# DAC.net
KiCad netlist of a schematic drawn in Altium Designer
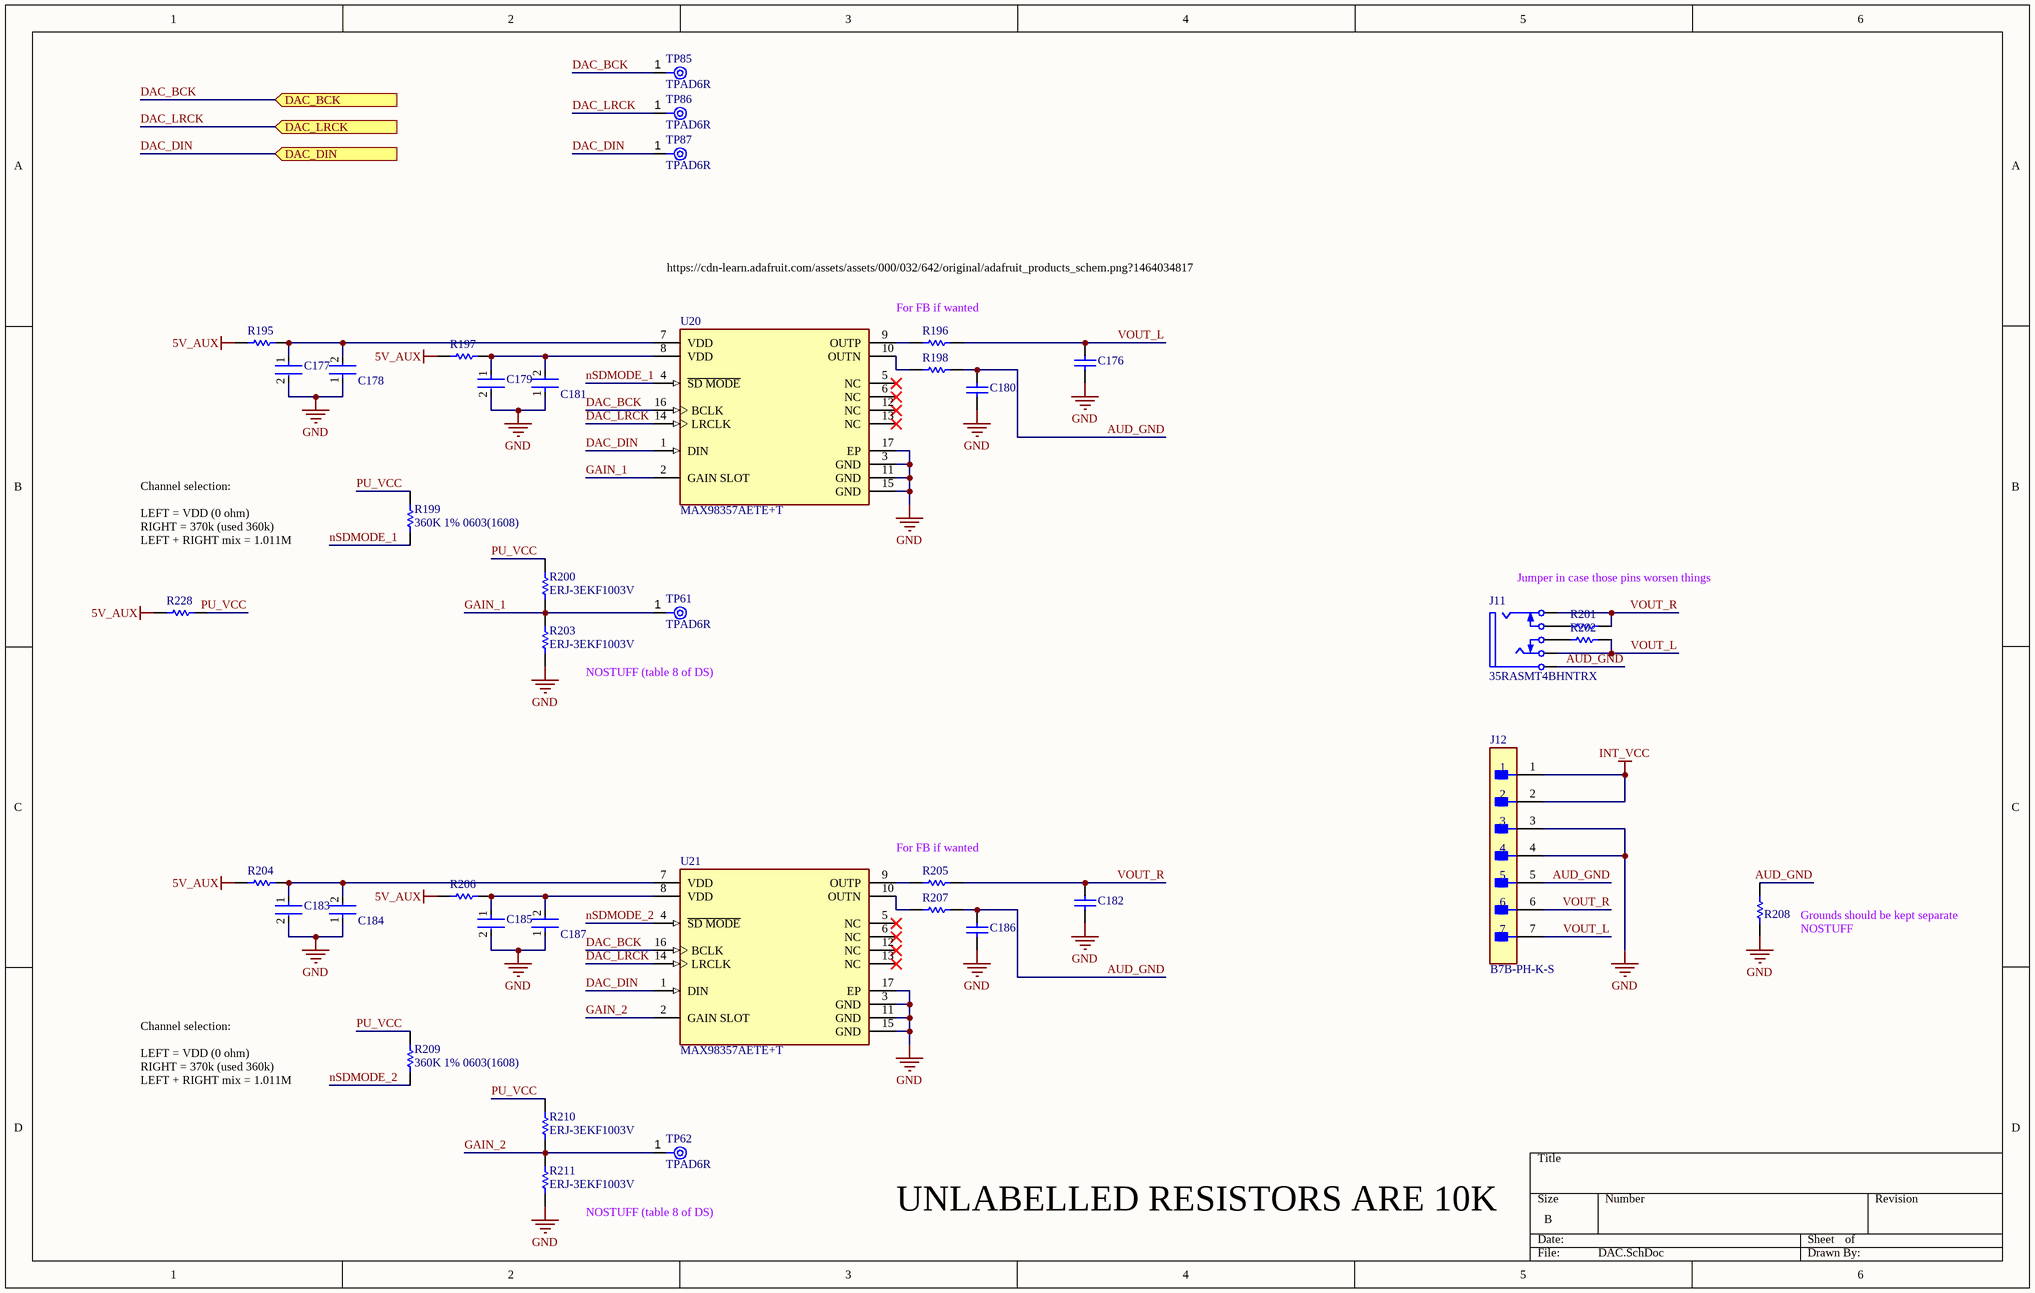
[diagram p0: DAC.SchDoc]

(export (version "E")
  (design (tool "Eeschema 10.0.6"))
  (components
    (comp (ref "C176")
      (value "C0805C221K5RACTU")
      (footprint "CAPC2013X88X50ML20T25")
      (fields (field (name "MANUFACTURER") "Kemet"))
      (libsource (lib "Altium Content Vault") (part "CAP"))
    )
    (comp (ref "C177")
      (value "CL05A106MP5NUNC")
      (footprint "FP-CL05A106MP5NUNC-MFG")
      (description "CAP CER 10UF 10V X5R 0402")
      (fields
        (field (name "OCTOPART") "https://octopart.com/cl05a106mp5nunc-samsung-22457395")
        (field (name "TOLERANCE") "20%")
      )
      (libsource (lib "Altium Content Vault") (part "b4654b650e69147ec39a6b967a45e02"))
    )
    (comp (ref "C178")
      (value "C1005X7R1H104K050BB")
      (footprint "FP-C1005-050-0_05-IPC_C")
      (description "Multilayer Ceramic Capacitors 100nF ±10% 50V X7R SMD 0402")
      (fields (field (name "VOLTAGE") "50V") (field (name "TOLERANCE") "10%"))
      (libsource (lib "Altium Content Vault") (part "b4654b650e69147ec39a6b967a45e02"))
    )
    (comp (ref "C179")
      (value "CL05A106MP5NUNC")
      (footprint "FP-CL05A106MP5NUNC-MFG")
      (description "CAP CER 10UF 10V X5R 0402")
      (fields
        (field (name "OCTOPART") "https://octopart.com/cl05a106mp5nunc-samsung-22457395")
        (field (name "TOLERANCE") "20%")
      )
      (libsource (lib "Altium Content Vault") (part "b4654b650e69147ec39a6b967a45e02"))
    )
    (comp (ref "C180")
      (value "C0805C221K5RACTU")
      (footprint "CAPC2013X88X50ML20T25")
      (fields (field (name "MANUFACTURER") "Kemet"))
      (libsource (lib "Altium Content Vault") (part "CAP"))
    )
    (comp (ref "C181")
      (value "C1005X7R1H104K050BB")
      (footprint "FP-C1005-050-0_05-IPC_C")
      (description "Multilayer Ceramic Capacitors 100nF ±10% 50V X7R SMD 0402")
      (fields (field (name "VOLTAGE") "50V") (field (name "TOLERANCE") "10%"))
      (libsource (lib "Altium Content Vault") (part "b4654b650e69147ec39a6b967a45e02"))
    )
    (comp (ref "C182")
      (value "C0805C221K5RACTU")
      (footprint "CAPC2013X88X50ML20T25")
      (fields (field (name "MANUFACTURER") "Kemet"))
      (libsource (lib "Altium Content Vault") (part "CAP"))
    )
    (comp (ref "C183")
      (value "CL05A106MP5NUNC")
      (footprint "FP-CL05A106MP5NUNC-MFG")
      (description "CAP CER 10UF 10V X5R 0402")
      (fields
        (field (name "OCTOPART") "https://octopart.com/cl05a106mp5nunc-samsung-22457395")
        (field (name "TOLERANCE") "20%")
      )
      (libsource (lib "Altium Content Vault") (part "b4654b650e69147ec39a6b967a45e02"))
    )
    (comp (ref "C184")
      (value "C1005X7R1H104K050BB")
      (footprint "FP-C1005-050-0_05-IPC_C")
      (description "Multilayer Ceramic Capacitors 100nF ±10% 50V X7R SMD 0402")
      (fields (field (name "VOLTAGE") "50V") (field (name "TOLERANCE") "10%"))
      (libsource (lib "Altium Content Vault") (part "b4654b650e69147ec39a6b967a45e02"))
    )
    (comp (ref "C185")
      (value "CL05A106MP5NUNC")
      (footprint "FP-CL05A106MP5NUNC-MFG")
      (description "CAP CER 10UF 10V X5R 0402")
      (fields
        (field (name "OCTOPART") "https://octopart.com/cl05a106mp5nunc-samsung-22457395")
        (field (name "TOLERANCE") "20%")
      )
      (libsource (lib "Altium Content Vault") (part "b4654b650e69147ec39a6b967a45e02"))
    )
    (comp (ref "C186")
      (value "C0805C221K5RACTU")
      (footprint "CAPC2013X88X50ML20T25")
      (fields (field (name "MANUFACTURER") "Kemet"))
      (libsource (lib "Altium Content Vault") (part "CAP"))
    )
    (comp (ref "C187")
      (value "C1005X7R1H104K050BB")
      (footprint "FP-C1005-050-0_05-IPC_C")
      (description "Multilayer Ceramic Capacitors 100nF ±10% 50V X7R SMD 0402")
      (fields (field (name "VOLTAGE") "50V") (field (name "TOLERANCE") "10%"))
      (libsource (lib "Altium Content Vault") (part "b4654b650e69147ec39a6b967a45e02"))
    )
    (comp (ref "J11")
      (value "35RASMT4BHNTRX")
      (footprint "SWIT-35RASMT4BHNTRX_V")
      (description "Female 3.5 mm Phone Jack, 5 Position, Height 5 mm, RoHS, Tape and Reel")
      (libsource (lib "Altium Content Vault") (part "JACK-3CD5-RN"))
    )
    (comp (ref "J12")
      (value "B7B-PH-K-S")
      (footprint "FP-B7B-PH-K-S-MFG")
      (description "CONN HEADER VERT 7POS 2MM")
      (libsource (lib "Altium Content Vault") (part "5bcee6b94e1fee4be3f4cc3a650a442"))
    )
    (comp (ref "R195")
      (value "RC0402JR-070RL")
      (footprint "RESC1005X40X25NL05T10")
      (fields (field (name "MANUFACTURER") "Yageo / Phycomp"))
      (libsource (lib "Altium Content Vault") (part "RES"))
    )
    (comp (ref "R196")
      (value "RC0603JR-070RL")
      (footprint "RESC1608X55X25ML10T15")
      (description "Chip Resistor, 0 Ohm, +/- 5%, 0.1 W, -55 to 155 degC, 0603 (1608 Metric), RoHS, Tape and Reel")
      (fields (field (name "TOLERANCE") "5%") (field (name "MANUFACTURER") "Yageo"))
      (libsource (lib "Altium Content Vault") (part "RES-2"))
    )
    (comp (ref "R197")
      (value "RC0402JR-070RL")
      (footprint "RESC1005X40X25NL05T10")
      (fields (field (name "MANUFACTURER") "Yageo / Phycomp"))
      (libsource (lib "Altium Content Vault") (part "RES"))
    )
    (comp (ref "R198")
      (value "RC0603JR-070RL")
      (footprint "RESC1608X55X25ML10T15")
      (description "Chip Resistor, 0 Ohm, +/- 5%, 0.1 W, -55 to 155 degC, 0603 (1608 Metric), RoHS, Tape and Reel")
      (fields (field (name "TOLERANCE") "5%") (field (name "MANUFACTURER") "Yageo"))
      (libsource (lib "Altium Content Vault") (part "RES-2"))
    )
    (comp (ref "R199")
      (value "360K 1% 0603(1608)")
      (footprint "RESC0603(1608)_M")
      (description "360K 0.1W 1% 0603 (1608 Metric)  SMD")
      (fields (field (name "POWER") "0.1 W") (field (name "TOLERANCE") "1 %"))
      (libsource (lib "Altium Content Vault") (part "RES"))
    )
    (comp (ref "R200")
      (value "ERJ-3EKF1003V")
      (footprint "RESC1608X55X30ML15T15")
      (fields (field (name "MANUFACTURER") "Panasonic"))
      (libsource (lib "Altium Content Vault") (part "RES"))
    )
    (comp (ref "R201")
      (value "RC0402JR-070RL")
      (footprint "RESC1005X40X25NL05T10")
      (fields (field (name "MANUFACTURER") "Yageo / Phycomp"))
      (libsource (lib "Altium Content Vault") (part "RES"))
    )
    (comp (ref "R202")
      (value "RC0402JR-070RL")
      (footprint "RESC1005X40X25NL05T10")
      (fields (field (name "MANUFACTURER") "Yageo / Phycomp"))
      (libsource (lib "Altium Content Vault") (part "RES"))
    )
    (comp (ref "R203")
      (value "ERJ-3EKF1003V")
      (footprint "RESC1608X55X30ML15T15")
      (fields (field (name "MANUFACTURER") "Panasonic"))
      (libsource (lib "Altium Content Vault") (part "RES"))
    )
    (comp (ref "R204")
      (value "RC0402JR-070RL")
      (footprint "RESC1005X40X25NL05T10")
      (fields (field (name "MANUFACTURER") "Yageo / Phycomp"))
      (libsource (lib "Altium Content Vault") (part "RES"))
    )
    (comp (ref "R205")
      (value "RC0603JR-070RL")
      (footprint "RESC1608X55X25ML10T15")
      (description "Chip Resistor, 0 Ohm, +/- 5%, 0.1 W, -55 to 155 degC, 0603 (1608 Metric), RoHS, Tape and Reel")
      (fields (field (name "TOLERANCE") "5%") (field (name "MANUFACTURER") "Yageo"))
      (libsource (lib "Altium Content Vault") (part "RES-2"))
    )
    (comp (ref "R206")
      (value "RC0402JR-070RL")
      (footprint "RESC1005X40X25NL05T10")
      (fields (field (name "MANUFACTURER") "Yageo / Phycomp"))
      (libsource (lib "Altium Content Vault") (part "RES"))
    )
    (comp (ref "R207")
      (value "RC0603JR-070RL")
      (footprint "RESC1608X55X25ML10T15")
      (description "Chip Resistor, 0 Ohm, +/- 5%, 0.1 W, -55 to 155 degC, 0603 (1608 Metric), RoHS, Tape and Reel")
      (fields (field (name "TOLERANCE") "5%") (field (name "MANUFACTURER") "Yageo"))
      (libsource (lib "Altium Content Vault") (part "RES-2"))
    )
    (comp (ref "R208")
      (value "RC0603JR-070RL")
      (footprint "RESC1608X55X25ML10T15")
      (description "Chip Resistor, 0 Ohm, +/- 5%, 0.1 W, -55 to 155 degC, 0603 (1608 Metric), RoHS, Tape and Reel")
      (fields (field (name "TOLERANCE") "5%") (field (name "MANUFACTURER") "Yageo"))
      (libsource (lib "Altium Content Vault") (part "RES-2"))
    )
    (comp (ref "R209")
      (value "360K 1% 0603(1608)")
      (footprint "RESC0603(1608)_M")
      (description "360K 0.1W 1% 0603 (1608 Metric)  SMD")
      (fields (field (name "POWER") "0.1 W") (field (name "TOLERANCE") "1 %"))
      (libsource (lib "Altium Content Vault") (part "RES"))
    )
    (comp (ref "R210")
      (value "ERJ-3EKF1003V")
      (footprint "RESC1608X55X30ML15T15")
      (fields (field (name "MANUFACTURER") "Panasonic"))
      (libsource (lib "Altium Content Vault") (part "RES"))
    )
    (comp (ref "R211")
      (value "ERJ-3EKF1003V")
      (footprint "RESC1608X55X30ML15T15")
      (fields (field (name "MANUFACTURER") "Panasonic"))
      (libsource (lib "Altium Content Vault") (part "RES"))
    )
    (comp (ref "R228")
      (value "RC0402JR-070RL")
      (footprint "RESC1005X40X25NL05T10")
      (fields (field (name "MANUFACTURER") "Yageo / Phycomp"))
      (libsource (lib "Altium Content Vault") (part "RES"))
    )
    (comp (ref "TP61")
      (value "TPAD6R")
      (footprint "New footprint 1")
      (description "Test Point .6mm")
      (libsource (lib "Space Concordia") (part "TP"))
    )
    (comp (ref "TP62")
      (value "TPAD6R")
      (footprint "New footprint 1")
      (description "Test Point .6mm")
      (libsource (lib "Space Concordia") (part "TP"))
    )
    (comp (ref "TP85")
      (value "TPAD6R")
      (footprint "New footprint 1")
      (description "Test Point .6mm")
      (libsource (lib "Space Concordia") (part "TP"))
    )
    (comp (ref "TP86")
      (value "TPAD6R")
      (footprint "New footprint 1")
      (description "Test Point .6mm")
      (libsource (lib "Space Concordia") (part "TP"))
    )
    (comp (ref "TP87")
      (value "TPAD6R")
      (footprint "New footprint 1")
      (description "Test Point .6mm")
      (libsource (lib "Space Concordia") (part "TP"))
    )
    (comp (ref "U20")
      (value "MAX98357AETE+T")
      (footprint "FP-T1633-4-MFG")
      (description "IC AMP CLASS D MONO 3.2W 16TQFN")
      (libsource (lib "Altium Content Vault") (part "902df0143a84dfa2dd990dcc5368a09"))
    )
    (comp (ref "U21")
      (value "MAX98357AETE+T")
      (footprint "FP-T1633-4-MFG")
      (description "IC AMP CLASS D MONO 3.2W 16TQFN")
      (libsource (lib "Altium Content Vault") (part "902df0143a84dfa2dd990dcc5368a09"))
    )
  )
  (nets
    (net (code "1") (name "/AUD_GND") (class "Default")
      (node (ref "C180") (pin "2") (pinfunction "2_2") (pintype "passive"))
      (node (ref "C186") (pin "2") (pinfunction "2_2") (pintype "passive"))
      (node (ref "J11") (pin "1") (pinfunction "1_1") (pintype "passive"))
      (node (ref "J12") (pin "5") (pinfunction "5_5") (pintype "passive"))
      (node (ref "R198") (pin "2") (pinfunction "2_2") (pintype "passive"))
      (node (ref "R207") (pin "2") (pinfunction "2_2") (pintype "passive"))
      (node (ref "R208") (pin "1") (pinfunction "1_1") (pintype "passive"))
    )
    (net (code "2") (name "/DAC_BCK") (class "Default")
      (node (ref "TP85") (pin "1") (pinfunction "TP_1") (pintype "passive"))
      (node (ref "U20") (pin "16") (pinfunction "BCLK_16") (pintype "input"))
      (node (ref "U21") (pin "16") (pinfunction "BCLK_16") (pintype "input"))
    )
    (net (code "3") (name "/DAC_DIN") (class "Default")
      (node (ref "TP87") (pin "1") (pinfunction "TP_1") (pintype "passive"))
      (node (ref "U20") (pin "1") (pinfunction "DIN_1") (pintype "input"))
      (node (ref "U21") (pin "1") (pinfunction "DIN_1") (pintype "input"))
    )
    (net (code "4") (name "/DAC_LRCK") (class "Default")
      (node (ref "TP86") (pin "1") (pinfunction "TP_1") (pintype "passive"))
      (node (ref "U20") (pin "14") (pinfunction "LRCLK_14") (pintype "input"))
      (node (ref "U21") (pin "14") (pinfunction "LRCLK_14") (pintype "input"))
    )
    (net (code "5") (name "/GAIN_1") (class "Default")
      (node (ref "R200") (pin "1") (pinfunction "1_1") (pintype "passive"))
      (node (ref "R203") (pin "2") (pinfunction "2_2") (pintype "passive"))
      (node (ref "TP61") (pin "1") (pinfunction "TP_1") (pintype "passive"))
      (node (ref "U20") (pin "2") (pinfunction "GAIN_SLOT_2") (pintype "passive"))
    )
    (net (code "6") (name "/GAIN_2") (class "Default")
      (node (ref "R210") (pin "1") (pinfunction "1_1") (pintype "passive"))
      (node (ref "R211") (pin "2") (pinfunction "2_2") (pintype "passive"))
      (node (ref "TP62") (pin "1") (pinfunction "TP_1") (pintype "passive"))
      (node (ref "U21") (pin "2") (pinfunction "GAIN_SLOT_2") (pintype "passive"))
    )
    (net (code "7") (name "/PU_VCC") (class "Default")
      (node (ref "R199") (pin "2") (pinfunction "2_2") (pintype "passive"))
      (node (ref "R200") (pin "2") (pinfunction "2_2") (pintype "passive"))
      (node (ref "R209") (pin "2") (pinfunction "2_2") (pintype "passive"))
      (node (ref "R210") (pin "2") (pinfunction "2_2") (pintype "passive"))
      (node (ref "R228") (pin "2") (pinfunction "2_2") (pintype "passive"))
    )
    (net (code "8") (name "/VOUT_L") (class "Default")
      (node (ref "C176") (pin "2") (pinfunction "2_2") (pintype "passive"))
      (node (ref "J11") (pin "3") (pinfunction "3_3") (pintype "passive"))
      (node (ref "J12") (pin "7") (pinfunction "7_7") (pintype "passive"))
      (node (ref "R196") (pin "2") (pinfunction "2_2") (pintype "passive"))
      (node (ref "R202") (pin "2") (pinfunction "2_2") (pintype "passive"))
    )
    (net (code "9") (name "/VOUT_R") (class "Default")
      (node (ref "C182") (pin "2") (pinfunction "2_2") (pintype "passive"))
      (node (ref "J11") (pin "2") (pinfunction "2_2") (pintype "passive"))
      (node (ref "J12") (pin "6") (pinfunction "6_6") (pintype "passive"))
      (node (ref "R201") (pin "2") (pinfunction "2_2") (pintype "passive"))
      (node (ref "R205") (pin "2") (pinfunction "2_2") (pintype "passive"))
    )
    (net (code "10") (name "/nSDMODE_1") (class "Default")
      (node (ref "R199") (pin "1") (pinfunction "1_1") (pintype "passive"))
      (node (ref "U20") (pin "4") (pinfunction "~{SD_MODE}_4") (pintype "input"))
    )
    (net (code "11") (name "/nSDMODE_2") (class "Default")
      (node (ref "R209") (pin "1") (pinfunction "1_1") (pintype "passive"))
      (node (ref "U21") (pin "4") (pinfunction "~{SD_MODE}_4") (pintype "input"))
    )
    (net (code "12") (name "5V_AUX") (class "Default")
      (node (ref "R195") (pin "1") (pinfunction "1_1") (pintype "passive"))
      (node (ref "R197") (pin "1") (pinfunction "1_1") (pintype "passive"))
      (node (ref "R204") (pin "1") (pinfunction "1_1") (pintype "passive"))
      (node (ref "R206") (pin "1") (pinfunction "1_1") (pintype "passive"))
      (node (ref "R228") (pin "1") (pinfunction "1_1") (pintype "passive"))
    )
    (net (code "13") (name "GND") (class "Default")
      (node (ref "C176") (pin "1") (pinfunction "1_1") (pintype "passive"))
      (node (ref "C177") (pin "2") (pinfunction "2_2") (pintype "passive"))
      (node (ref "C178") (pin "1") (pinfunction "1_1") (pintype "passive"))
      (node (ref "C179") (pin "2") (pinfunction "2_2") (pintype "passive"))
      (node (ref "C180") (pin "1") (pinfunction "1_1") (pintype "passive"))
      (node (ref "C181") (pin "1") (pinfunction "1_1") (pintype "passive"))
      (node (ref "C182") (pin "1") (pinfunction "1_1") (pintype "passive"))
      (node (ref "C183") (pin "2") (pinfunction "2_2") (pintype "passive"))
      (node (ref "C184") (pin "1") (pinfunction "1_1") (pintype "passive"))
      (node (ref "C185") (pin "2") (pinfunction "2_2") (pintype "passive"))
      (node (ref "C186") (pin "1") (pinfunction "1_1") (pintype "passive"))
      (node (ref "C187") (pin "1") (pinfunction "1_1") (pintype "passive"))
      (node (ref "J12") (pin "3") (pinfunction "3_3") (pintype "passive"))
      (node (ref "J12") (pin "4") (pinfunction "4_4") (pintype "passive"))
      (node (ref "R203") (pin "1") (pinfunction "1_1") (pintype "passive"))
      (node (ref "R208") (pin "2") (pinfunction "2_2") (pintype "passive"))
      (node (ref "R211") (pin "1") (pinfunction "1_1") (pintype "passive"))
      (node (ref "U20") (pin "11") (pinfunction "GND_11") (pintype "power_in"))
      (node (ref "U20") (pin "15") (pinfunction "GND_15") (pintype "power_in"))
      (node (ref "U20") (pin "17") (pinfunction "EP_17") (pintype "passive"))
      (node (ref "U20") (pin "3") (pinfunction "GND_3") (pintype "power_in"))
      (node (ref "U21") (pin "11") (pinfunction "GND_11") (pintype "power_in"))
      (node (ref "U21") (pin "15") (pinfunction "GND_15") (pintype "power_in"))
      (node (ref "U21") (pin "17") (pinfunction "EP_17") (pintype "passive"))
      (node (ref "U21") (pin "3") (pinfunction "GND_3") (pintype "power_in"))
    )
    (net (code "14") (name "INT_VCC") (class "Default")
      (node (ref "J12") (pin "1") (pinfunction "1_1") (pintype "passive"))
      (node (ref "J12") (pin "2") (pinfunction "2_2") (pintype "passive"))
    )
    (net (code "15") (name "Net-(C177-Pad1)") (class "Default")
      (node (ref "C177") (pin "1") (pinfunction "1_1") (pintype "passive"))
      (node (ref "C178") (pin "2") (pinfunction "2_2") (pintype "passive"))
      (node (ref "R195") (pin "2") (pinfunction "2_2") (pintype "passive"))
      (node (ref "U20") (pin "7") (pinfunction "VDD_7") (pintype "power_in"))
    )
    (net (code "16") (name "Net-(C179-Pad1)") (class "Default")
      (node (ref "C179") (pin "1") (pinfunction "1_1") (pintype "passive"))
      (node (ref "C181") (pin "2") (pinfunction "2_2") (pintype "passive"))
      (node (ref "R197") (pin "2") (pinfunction "2_2") (pintype "passive"))
      (node (ref "U20") (pin "8") (pinfunction "VDD_8") (pintype "power_in"))
    )
    (net (code "17") (name "Net-(C183-Pad1)") (class "Default")
      (node (ref "C183") (pin "1") (pinfunction "1_1") (pintype "passive"))
      (node (ref "C184") (pin "2") (pinfunction "2_2") (pintype "passive"))
      (node (ref "R204") (pin "2") (pinfunction "2_2") (pintype "passive"))
      (node (ref "U21") (pin "7") (pinfunction "VDD_7") (pintype "power_in"))
    )
    (net (code "18") (name "Net-(C185-Pad1)") (class "Default")
      (node (ref "C185") (pin "1") (pinfunction "1_1") (pintype "passive"))
      (node (ref "C187") (pin "2") (pinfunction "2_2") (pintype "passive"))
      (node (ref "R206") (pin "2") (pinfunction "2_2") (pintype "passive"))
      (node (ref "U21") (pin "8") (pinfunction "VDD_8") (pintype "power_in"))
    )
    (net (code "19") (name "Net-(J11-Pad4)") (class "Default")
      (node (ref "J11") (pin "4") (pinfunction "4_4") (pintype "passive"))
      (node (ref "R201") (pin "1") (pinfunction "1_1") (pintype "passive"))
    )
    (net (code "20") (name "Net-(J11-Pad5)") (class "Default")
      (node (ref "J11") (pin "5") (pinfunction "5_5") (pintype "passive"))
      (node (ref "R202") (pin "1") (pinfunction "1_1") (pintype "passive"))
    )
    (net (code "21") (name "Net-(U20-OUTN)") (class "Default")
      (node (ref "R198") (pin "1") (pinfunction "1_1") (pintype "passive"))
      (node (ref "U20") (pin "10") (pinfunction "OUTN_10") (pintype "passive"))
    )
    (net (code "22") (name "Net-(U20-OUTP)") (class "Default")
      (node (ref "R196") (pin "1") (pinfunction "1_1") (pintype "passive"))
      (node (ref "U20") (pin "9") (pinfunction "OUTP_9") (pintype "passive"))
    )
    (net (code "23") (name "Net-(U21-OUTN)") (class "Default")
      (node (ref "R207") (pin "1") (pinfunction "1_1") (pintype "passive"))
      (node (ref "U21") (pin "10") (pinfunction "OUTN_10") (pintype "passive"))
    )
    (net (code "24") (name "Net-(U21-OUTP)") (class "Default")
      (node (ref "R205") (pin "1") (pinfunction "1_1") (pintype "passive"))
      (node (ref "U21") (pin "9") (pinfunction "OUTP_9") (pintype "passive"))
    )
    (net (code "25") (name "unconnected-(U20-NC-Pad5)") (class "Default")
      (node (ref "U20") (pin "5") (pinfunction "NC_5") (pintype "passive+no_connect"))
    )
    (net (code "26") (name "unconnected-(U20-NC-Pad6)") (class "Default")
      (node (ref "U20") (pin "6") (pinfunction "NC_6") (pintype "passive+no_connect"))
    )
    (net (code "27") (name "unconnected-(U20-NC-Pad12)") (class "Default")
      (node (ref "U20") (pin "12") (pinfunction "NC_12") (pintype "passive+no_connect"))
    )
    (net (code "28") (name "unconnected-(U20-NC-Pad13)") (class "Default")
      (node (ref "U20") (pin "13") (pinfunction "NC_13") (pintype "passive+no_connect"))
    )
    (net (code "29") (name "unconnected-(U21-NC-Pad5)") (class "Default")
      (node (ref "U21") (pin "5") (pinfunction "NC_5") (pintype "passive+no_connect"))
    )
    (net (code "30") (name "unconnected-(U21-NC-Pad6)") (class "Default")
      (node (ref "U21") (pin "6") (pinfunction "NC_6") (pintype "passive+no_connect"))
    )
    (net (code "31") (name "unconnected-(U21-NC-Pad12)") (class "Default")
      (node (ref "U21") (pin "12") (pinfunction "NC_12") (pintype "passive+no_connect"))
    )
    (net (code "32") (name "unconnected-(U21-NC-Pad13)") (class "Default")
      (node (ref "U21") (pin "13") (pinfunction "NC_13") (pintype "passive+no_connect"))
    )
  )
)
